# ADCduinoModule_ADC.net
KiCad netlist of a schematic drawn in Altium Designer
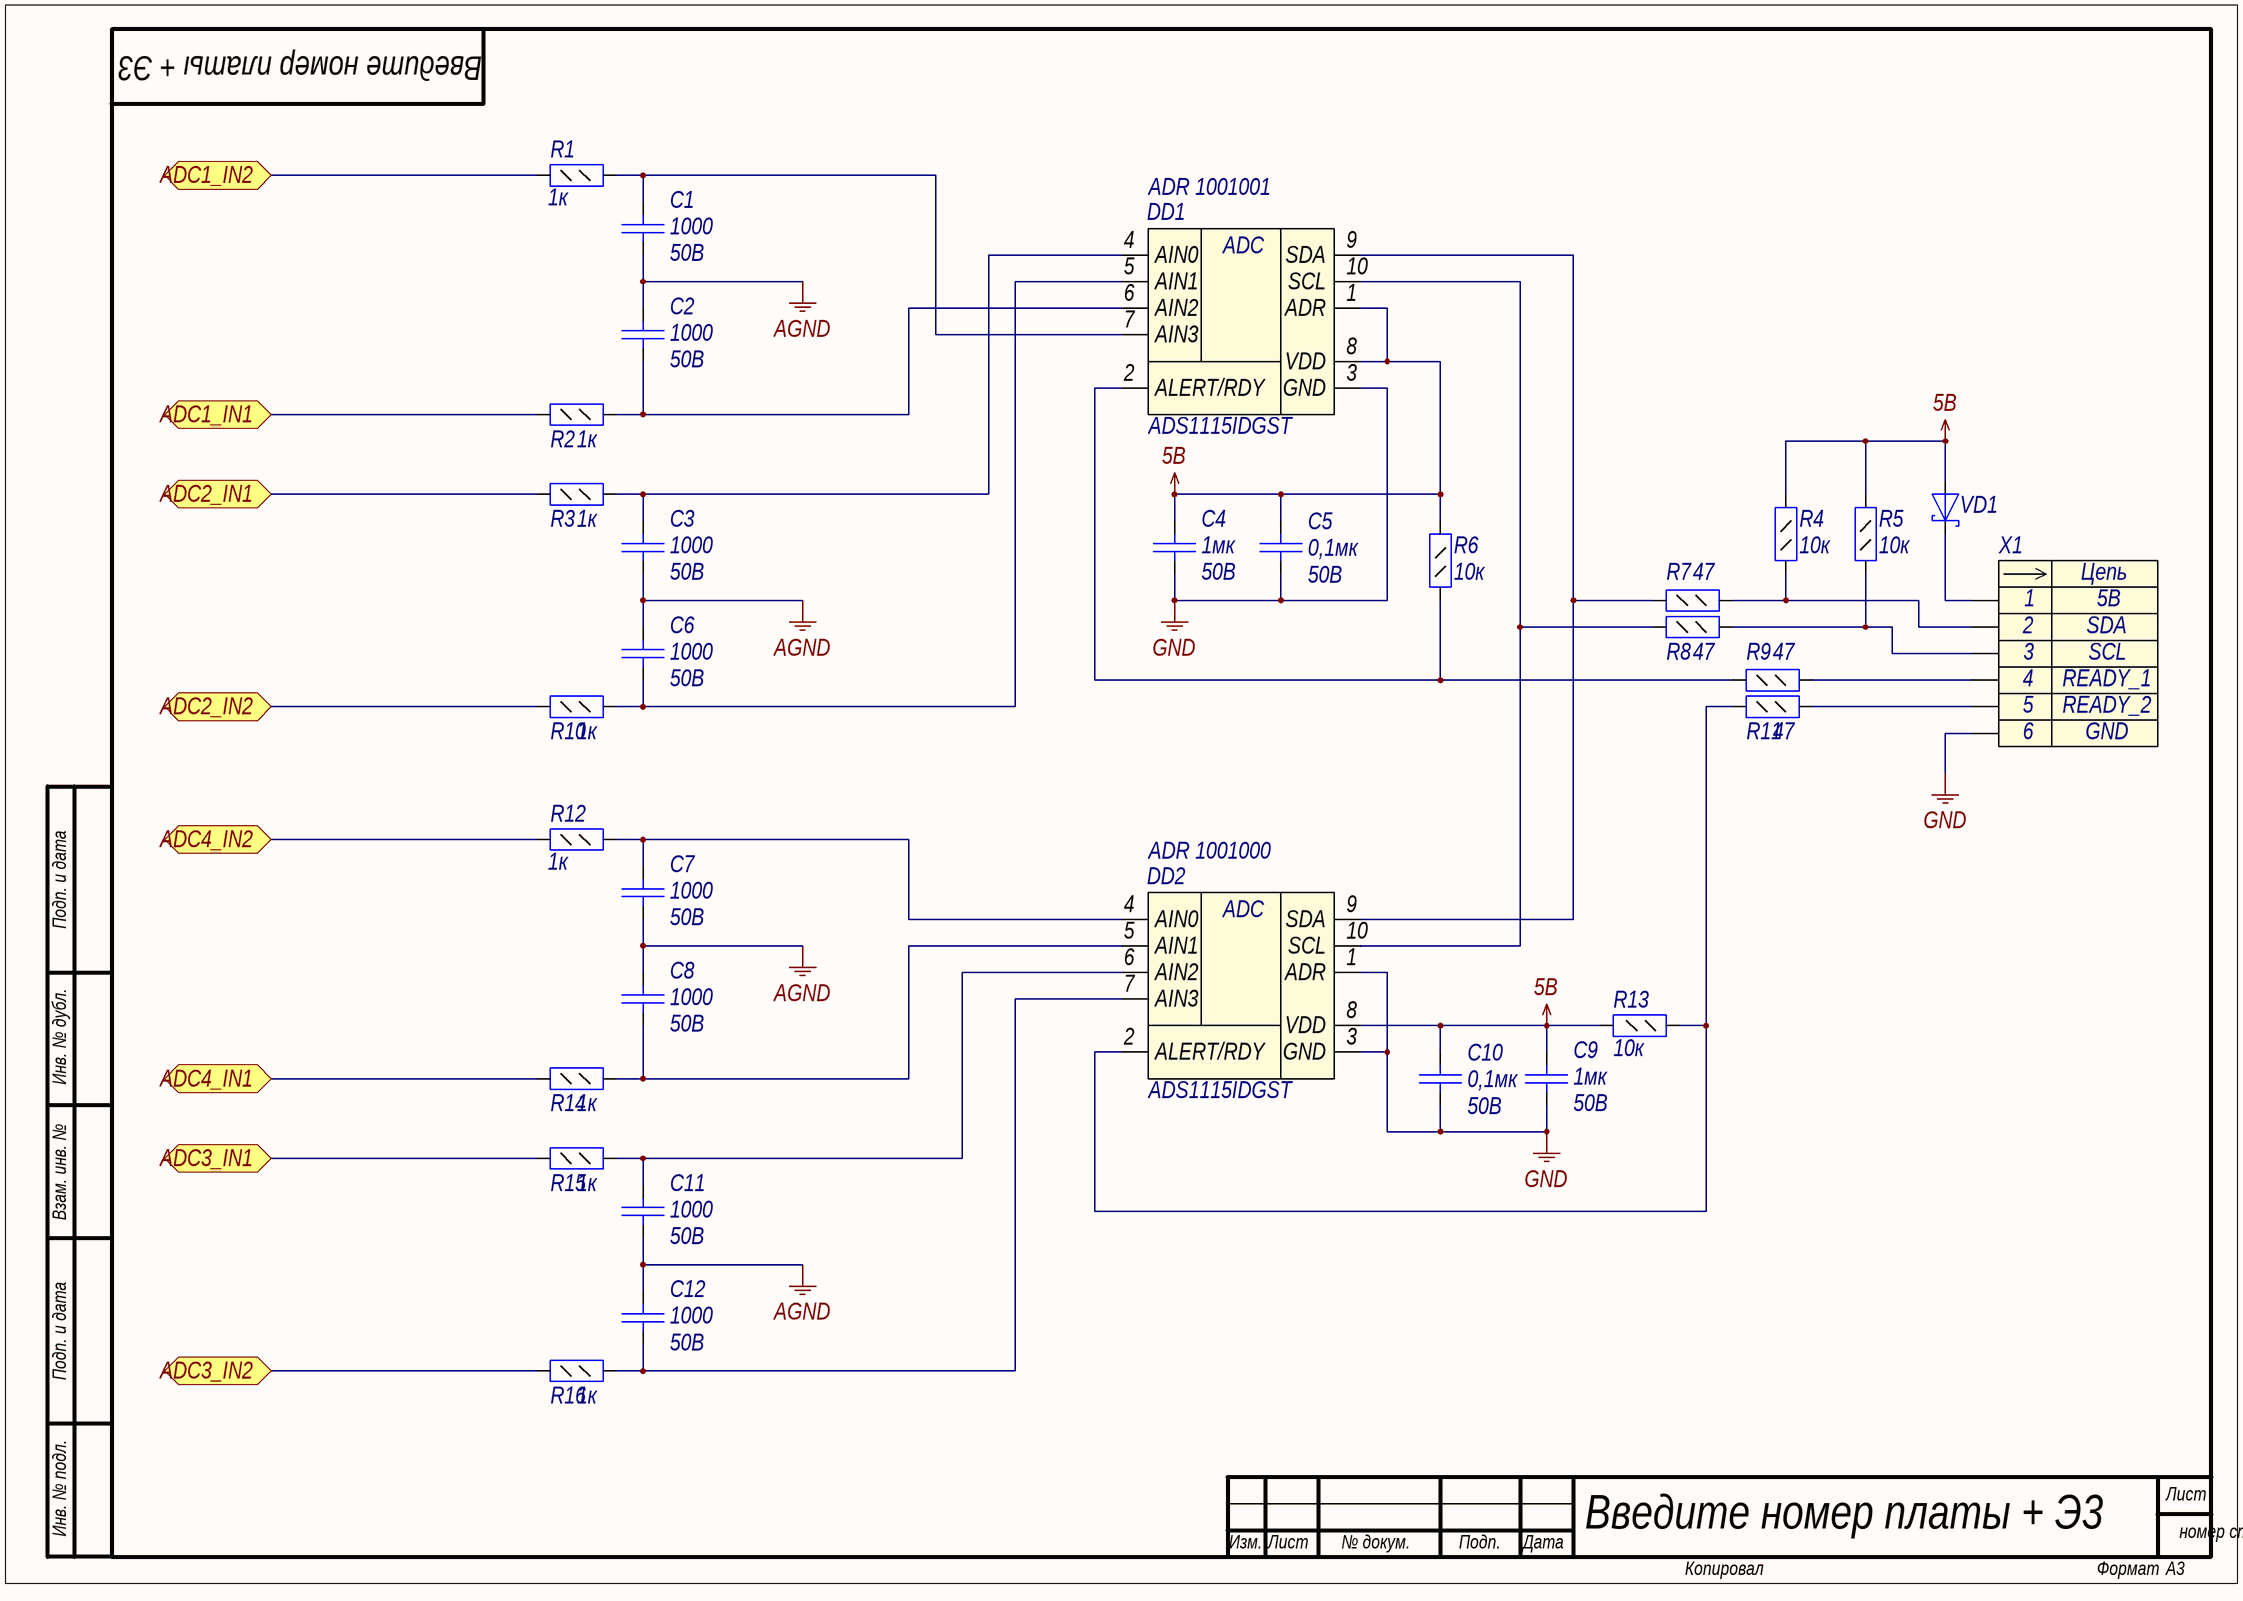
[diagram p0: ADCduinoModule_ADC.SchDoc]

(export (version "E")
  (design (tool "Eeschema 10.0.6"))
  (components
    (comp (ref "C1")
      (value "1000")
      (footprint "C0805")
      (description "Конденсатор")
      (fields
        (field (name "VOLTAGE") "50В")
        (field (name "PART NUMBER") "GRM216R71H102K*")
        (field (name "Comment") "Capacitor")
      )
      (libsource (lib "MOP44") (part "Capacitor"))
    )
    (comp (ref "C2")
      (value "1000")
      (footprint "C0805")
      (description "Конденсатор")
      (fields
        (field (name "VOLTAGE") "50В")
        (field (name "PART NUMBER") "GRM216R71H102K*")
        (field (name "Comment") "Capacitor")
      )
      (libsource (lib "MOP44") (part "Capacitor"))
    )
    (comp (ref "C3")
      (value "1000")
      (footprint "C0805")
      (description "Конденсатор")
      (fields
        (field (name "VOLTAGE") "50В")
        (field (name "PART NUMBER") "GRM216R71H102K*")
        (field (name "Comment") "Capacitor")
      )
      (libsource (lib "MOP44") (part "Capacitor"))
    )
    (comp (ref "C4")
      (value "1мк")
      (footprint "C0805")
      (description "Конденсатор")
      (fields
        (field (name "VOLTAGE") "50B")
        (field (name "PART NUMBER") "GRM21BR71H105K")
        (field (name "Comment") "Capacitor")
      )
      (libsource (lib "MOP44") (part "Capacitor"))
    )
    (comp (ref "C5")
      (value "0,1мк")
      (footprint "C0805")
      (description "Конденсатор")
      (fields
        (field (name "VOLTAGE") "50B")
        (field (name "PART NUMBER") "GRM21BR71H104K**")
        (field (name "Comment") "Capacitor")
      )
      (libsource (lib "MOP44") (part "Capacitor"))
    )
    (comp (ref "C6")
      (value "1000")
      (footprint "C0805")
      (description "Конденсатор")
      (fields
        (field (name "VOLTAGE") "50В")
        (field (name "PART NUMBER") "GRM216R71H102K*")
        (field (name "Comment") "Capacitor")
      )
      (libsource (lib "MOP44") (part "Capacitor"))
    )
    (comp (ref "C7")
      (value "1000")
      (footprint "C0805")
      (description "Конденсатор")
      (fields
        (field (name "VOLTAGE") "50В")
        (field (name "PART NUMBER") "GRM216R71H102K*")
        (field (name "Comment") "Capacitor")
      )
      (libsource (lib "MOP44") (part "Capacitor"))
    )
    (comp (ref "C8")
      (value "1000")
      (footprint "C0805")
      (description "Конденсатор")
      (fields
        (field (name "VOLTAGE") "50В")
        (field (name "PART NUMBER") "GRM216R71H102K*")
        (field (name "Comment") "Capacitor")
      )
      (libsource (lib "MOP44") (part "Capacitor"))
    )
    (comp (ref "C9")
      (value "1мк")
      (footprint "C0805")
      (description "Конденсатор")
      (fields
        (field (name "VOLTAGE") "50B")
        (field (name "PART NUMBER") "GRM21BR71H105K")
        (field (name "Comment") "Capacitor")
      )
      (libsource (lib "MOP44") (part "Capacitor"))
    )
    (comp (ref "C10")
      (value "0,1мк")
      (footprint "C0805")
      (description "Конденсатор")
      (fields
        (field (name "VOLTAGE") "50B")
        (field (name "PART NUMBER") "GRM21BR71H104K**")
        (field (name "Comment") "Capacitor")
      )
      (libsource (lib "MOP44") (part "Capacitor"))
    )
    (comp (ref "C11")
      (value "1000")
      (footprint "C0805")
      (description "Конденсатор")
      (fields
        (field (name "VOLTAGE") "50В")
        (field (name "PART NUMBER") "GRM216R71H102K*")
        (field (name "Comment") "Capacitor")
      )
      (libsource (lib "MOP44") (part "Capacitor"))
    )
    (comp (ref "C12")
      (value "1000")
      (footprint "C0805")
      (description "Конденсатор")
      (fields
        (field (name "VOLTAGE") "50В")
        (field (name "PART NUMBER") "GRM216R71H102K*")
        (field (name "Comment") "Capacitor")
      )
      (libsource (lib "MOP44") (part "Capacitor"))
    )
    (comp (ref "DD1")
      (value "ADS1115IDGST")
      (footprint "MSOP10")
      (description "Ultra-Small, Low-Power, 16-Bit  Analog-to-Digital Converter with Internal Reference")
      (libsource (lib "MOP44") (part "ADS1115IDGST"))
    )
    (comp (ref "DD2")
      (value "ADS1115IDGST")
      (footprint "MSOP10")
      (description "Ultra-Small, Low-Power, 16-Bit  Analog-to-Digital Converter with Internal Reference")
      (libsource (lib "MOP44") (part "ADS1115IDGST"))
    )
    (comp (ref "R1")
      (value "1к")
      (footprint "R0805")
      (description "Резистор")
      (fields (field (name "PART NUMBER") "RC0805FR-071KL") (field (name "POWER") "0,125Вт"))
      (libsource (lib "MOP44") (part "Resistor_0,125Вт"))
    )
    (comp (ref "R2")
      (value "1к")
      (footprint "R0805")
      (description "Резистор")
      (fields (field (name "PART NUMBER") "RC0805FR-071KL") (field (name "POWER") "0,125Вт"))
      (libsource (lib "MOP44") (part "Resistor_0,125Вт"))
    )
    (comp (ref "R3")
      (value "1к")
      (footprint "R0805")
      (description "Резистор")
      (fields (field (name "PART NUMBER") "RC0805FR-071KL") (field (name "POWER") "0,125Вт"))
      (libsource (lib "MOP44") (part "Resistor_0,125Вт"))
    )
    (comp (ref "R4")
      (value "10к")
      (footprint "R0805")
      (description "Резистор")
      (fields (field (name "PART NUMBER") "RC0805FR-0710KL") (field (name "POWER") "0,125Вт"))
      (libsource (lib "") (part "Resistor_0,125Вт_1"))
    )
    (comp (ref "R5")
      (value "10к")
      (footprint "R0805")
      (description "Резистор")
      (fields (field (name "PART NUMBER") "RC0805FR-0710KL") (field (name "POWER") "0,125Вт"))
      (libsource (lib "") (part "Resistor_0,125Вт_1"))
    )
    (comp (ref "R6")
      (value "10к")
      (footprint "R0805")
      (description "Резистор")
      (fields (field (name "PART NUMBER") "RC0805FR-0710KL") (field (name "POWER") "0,125Вт"))
      (libsource (lib "") (part "Resistor_0,125Вт_1"))
    )
    (comp (ref "R7")
      (value "47")
      (footprint "R0805")
      (description "Резистор")
      (fields (field (name "PART NUMBER") "RC0805FR-0747RL") (field (name "POWER") "0,125Вт"))
      (libsource (lib "MOP44") (part "Resistor_0,125Вт"))
    )
    (comp (ref "R8")
      (value "47")
      (footprint "R0805")
      (description "Резистор")
      (fields (field (name "PART NUMBER") "RC0805FR-0747RL") (field (name "POWER") "0,125Вт"))
      (libsource (lib "MOP44") (part "Resistor_0,125Вт"))
    )
    (comp (ref "R9")
      (value "47")
      (footprint "R0805")
      (description "Резистор")
      (fields (field (name "PART NUMBER") "RC0805FR-0747RL") (field (name "POWER") "0,125Вт"))
      (libsource (lib "MOP44") (part "Resistor_0,125Вт"))
    )
    (comp (ref "R10")
      (value "1к")
      (footprint "R0805")
      (description "Резистор")
      (fields (field (name "PART NUMBER") "RC0805FR-071KL") (field (name "POWER") "0,125Вт"))
      (libsource (lib "MOP44") (part "Resistor_0,125Вт"))
    )
    (comp (ref "R11")
      (value "47")
      (footprint "R0805")
      (description "Резистор")
      (fields (field (name "PART NUMBER") "RC0805FR-0747RL") (field (name "POWER") "0,125Вт"))
      (libsource (lib "MOP44") (part "Resistor_0,125Вт"))
    )
    (comp (ref "R12")
      (value "1к")
      (footprint "R0805")
      (description "Резистор")
      (fields (field (name "PART NUMBER") "RC0805FR-071KL") (field (name "POWER") "0,125Вт"))
      (libsource (lib "MOP44") (part "Resistor_0,125Вт"))
    )
    (comp (ref "R13")
      (value "10к")
      (footprint "R0805")
      (description "Резистор")
      (fields (field (name "PART NUMBER") "RC0805FR-0710KL") (field (name "POWER") "0,125Вт"))
      (libsource (lib "") (part "Resistor_0,125Вт_2"))
    )
    (comp (ref "R14")
      (value "1к")
      (footprint "R0805")
      (description "Резистор")
      (fields (field (name "PART NUMBER") "RC0805FR-071KL") (field (name "POWER") "0,125Вт"))
      (libsource (lib "MOP44") (part "Resistor_0,125Вт"))
    )
    (comp (ref "R15")
      (value "1к")
      (footprint "R0805")
      (description "Резистор")
      (fields (field (name "PART NUMBER") "RC0805FR-071KL") (field (name "POWER") "0,125Вт"))
      (libsource (lib "MOP44") (part "Resistor_0,125Вт"))
    )
    (comp (ref "R16")
      (value "1к")
      (footprint "R0805")
      (description "Резистор")
      (fields (field (name "PART NUMBER") "RC0805FR-071KL") (field (name "POWER") "0,125Вт"))
      (libsource (lib "MOP44") (part "Resistor_0,125Вт"))
    )
    (comp (ref "VD1")
      (value "DiodeSchottky")
      (footprint "SMA")
      (description "Диод Шоттки")
      (fields (field (name "PART NUMBER") "SK34A"))
      (libsource (lib "MOP44") (part "DiodeSchottky"))
    )
    (comp (ref "X1")
      (value "Header_6_plg")
      (footprint "PLS-6")
      (description "Разъем - 6 конт. вилка")
      (fields (field (name "PART NUMBER") "DS1021-1*6SF112-B"))
      (libsource (lib "MOP44") (part "Header_6_plg"))
    )
  )
  (nets
    (net (code "1") (name "/ADC1_IN1") (class "Default")
      (node (ref "R2") (pin "1") (pinfunction "1_1") (pintype "passive"))
    )
    (net (code "2") (name "/ADC1_IN2") (class "Default")
      (node (ref "R1") (pin "1") (pinfunction "1_1") (pintype "passive"))
    )
    (net (code "3") (name "/ADC2_IN1") (class "Default")
      (node (ref "R3") (pin "1") (pinfunction "1_1") (pintype "passive"))
    )
    (net (code "4") (name "/ADC2_IN2") (class "Default")
      (node (ref "R10") (pin "1") (pinfunction "1_1") (pintype "passive"))
    )
    (net (code "5") (name "/ADC3_IN1") (class "Default")
      (node (ref "R15") (pin "1") (pinfunction "1_1") (pintype "passive"))
    )
    (net (code "6") (name "/ADC3_IN2") (class "Default")
      (node (ref "R16") (pin "1") (pinfunction "1_1") (pintype "passive"))
    )
    (net (code "7") (name "/ADC4_IN1") (class "Default")
      (node (ref "R14") (pin "1") (pinfunction "1_1") (pintype "passive"))
    )
    (net (code "8") (name "/ADC4_IN2") (class "Default")
      (node (ref "R12") (pin "1") (pinfunction "1_1") (pintype "passive"))
    )
    (net (code "9") (name "5B") (class "Default")
      (node (ref "C10") (pin "2") (pinfunction "2_2") (pintype "passive"))
      (node (ref "C4") (pin "2") (pinfunction "2_2") (pintype "passive"))
      (node (ref "C5") (pin "2") (pinfunction "2_2") (pintype "passive"))
      (node (ref "C9") (pin "2") (pinfunction "2_2") (pintype "passive"))
      (node (ref "DD1") (pin "1") (pinfunction "ADR_1") (pintype "power_in"))
      (node (ref "DD1") (pin "8") (pinfunction "VDD_8") (pintype "power_in"))
      (node (ref "DD2") (pin "8") (pinfunction "VDD_8") (pintype "power_in"))
      (node (ref "R13") (pin "2") (pinfunction "2_2") (pintype "passive"))
      (node (ref "R4") (pin "2") (pinfunction "2_2") (pintype "passive"))
      (node (ref "R5") (pin "2") (pinfunction "2_2") (pintype "passive"))
      (node (ref "R6") (pin "2") (pinfunction "2_2") (pintype "passive"))
      (node (ref "VD1") (pin "2") (pinfunction "A_2") (pintype "passive"))
    )
    (net (code "10") (name "AGND") (class "Default")
      (node (ref "C1") (pin "1") (pinfunction "1_1") (pintype "passive"))
      (node (ref "C11") (pin "1") (pinfunction "1_1") (pintype "passive"))
      (node (ref "C12") (pin "2") (pinfunction "2_2") (pintype "passive"))
      (node (ref "C2") (pin "2") (pinfunction "2_2") (pintype "passive"))
      (node (ref "C3") (pin "1") (pinfunction "1_1") (pintype "passive"))
      (node (ref "C6") (pin "2") (pinfunction "2_2") (pintype "passive"))
      (node (ref "C7") (pin "1") (pinfunction "1_1") (pintype "passive"))
      (node (ref "C8") (pin "2") (pinfunction "2_2") (pintype "passive"))
    )
    (net (code "11") (name "GND") (class "Default")
      (node (ref "C10") (pin "1") (pinfunction "1_1") (pintype "passive"))
      (node (ref "C4") (pin "1") (pinfunction "1_1") (pintype "passive"))
      (node (ref "C5") (pin "1") (pinfunction "1_1") (pintype "passive"))
      (node (ref "C9") (pin "1") (pinfunction "1_1") (pintype "passive"))
      (node (ref "DD1") (pin "3") (pinfunction "GND_3") (pintype "power_in"))
      (node (ref "DD2") (pin "1") (pinfunction "ADR_1") (pintype "power_in"))
      (node (ref "DD2") (pin "3") (pinfunction "GND_3") (pintype "power_in"))
      (node (ref "X1") (pin "6") (pinfunction "6_6") (pintype "passive"))
    )
    (net (code "12") (name "Net-(DD1-AIN0)") (class "Default")
      (node (ref "C3") (pin "2") (pinfunction "2_2") (pintype "passive"))
      (node (ref "DD1") (pin "4") (pinfunction "AIN0_4") (pintype "power_in"))
      (node (ref "R3") (pin "2") (pinfunction "2_2") (pintype "passive"))
    )
    (net (code "13") (name "Net-(DD1-AIN1)") (class "Default")
      (node (ref "C6") (pin "1") (pinfunction "1_1") (pintype "passive"))
      (node (ref "DD1") (pin "5") (pinfunction "AIN1_5") (pintype "power_in"))
      (node (ref "R10") (pin "2") (pinfunction "2_2") (pintype "passive"))
    )
    (net (code "14") (name "Net-(DD1-AIN2)") (class "Default")
      (node (ref "C2") (pin "1") (pinfunction "1_1") (pintype "passive"))
      (node (ref "DD1") (pin "6") (pinfunction "AIN2_6") (pintype "power_in"))
      (node (ref "R2") (pin "2") (pinfunction "2_2") (pintype "passive"))
    )
    (net (code "15") (name "Net-(DD1-AIN3)") (class "Default")
      (node (ref "C1") (pin "2") (pinfunction "2_2") (pintype "passive"))
      (node (ref "DD1") (pin "7") (pinfunction "AIN3_7") (pintype "power_in"))
      (node (ref "R1") (pin "2") (pinfunction "2_2") (pintype "passive"))
    )
    (net (code "16") (name "Net-(DD1-ALERT{slash}RDY)") (class "Default")
      (node (ref "DD1") (pin "2") (pinfunction "ALERT/RDY_2") (pintype "power_in"))
      (node (ref "R6") (pin "1") (pinfunction "1_1") (pintype "passive"))
      (node (ref "R9") (pin "1") (pinfunction "1_1") (pintype "passive"))
    )
    (net (code "17") (name "Net-(DD1-SCL)") (class "Default")
      (node (ref "DD1") (pin "10") (pinfunction "SCL_10") (pintype "power_in"))
      (node (ref "DD2") (pin "10") (pinfunction "SCL_10") (pintype "power_in"))
      (node (ref "R8") (pin "1") (pinfunction "1_1") (pintype "passive"))
    )
    (net (code "18") (name "Net-(DD1-SDA)") (class "Default")
      (node (ref "DD1") (pin "9") (pinfunction "SDA_9") (pintype "power_in"))
      (node (ref "DD2") (pin "9") (pinfunction "SDA_9") (pintype "power_in"))
      (node (ref "R7") (pin "1") (pinfunction "1_1") (pintype "passive"))
    )
    (net (code "19") (name "Net-(DD2-AIN0)") (class "Default")
      (node (ref "C7") (pin "2") (pinfunction "2_2") (pintype "passive"))
      (node (ref "DD2") (pin "4") (pinfunction "AIN0_4") (pintype "power_in"))
      (node (ref "R12") (pin "2") (pinfunction "2_2") (pintype "passive"))
    )
    (net (code "20") (name "Net-(DD2-AIN1)") (class "Default")
      (node (ref "C8") (pin "1") (pinfunction "1_1") (pintype "passive"))
      (node (ref "DD2") (pin "5") (pinfunction "AIN1_5") (pintype "power_in"))
      (node (ref "R14") (pin "2") (pinfunction "2_2") (pintype "passive"))
    )
    (net (code "21") (name "Net-(DD2-AIN2)") (class "Default")
      (node (ref "C11") (pin "2") (pinfunction "2_2") (pintype "passive"))
      (node (ref "DD2") (pin "6") (pinfunction "AIN2_6") (pintype "power_in"))
      (node (ref "R15") (pin "2") (pinfunction "2_2") (pintype "passive"))
    )
    (net (code "22") (name "Net-(DD2-AIN3)") (class "Default")
      (node (ref "C12") (pin "1") (pinfunction "1_1") (pintype "passive"))
      (node (ref "DD2") (pin "7") (pinfunction "AIN3_7") (pintype "power_in"))
      (node (ref "R16") (pin "2") (pinfunction "2_2") (pintype "passive"))
    )
    (net (code "23") (name "Net-(DD2-ALERT{slash}RDY)") (class "Default")
      (node (ref "DD2") (pin "2") (pinfunction "ALERT/RDY_2") (pintype "power_in"))
      (node (ref "R11") (pin "1") (pinfunction "1_1") (pintype "passive"))
      (node (ref "R13") (pin "1") (pinfunction "1_1") (pintype "passive"))
    )
    (net (code "24") (name "Net-(R4-Pad1)") (class "Default")
      (node (ref "R4") (pin "1") (pinfunction "1_1") (pintype "passive"))
      (node (ref "R7") (pin "2") (pinfunction "2_2") (pintype "passive"))
      (node (ref "X1") (pin "2") (pinfunction "2_2") (pintype "passive"))
    )
    (net (code "25") (name "Net-(R5-Pad1)") (class "Default")
      (node (ref "R5") (pin "1") (pinfunction "1_1") (pintype "passive"))
      (node (ref "R8") (pin "2") (pinfunction "2_2") (pintype "passive"))
      (node (ref "X1") (pin "3") (pinfunction "3_3") (pintype "passive"))
    )
    (net (code "26") (name "Net-(R9-Pad2)") (class "Default")
      (node (ref "R9") (pin "2") (pinfunction "2_2") (pintype "passive"))
      (node (ref "X1") (pin "4") (pinfunction "4_4") (pintype "passive"))
    )
    (net (code "27") (name "Net-(R11-Pad2)") (class "Default")
      (node (ref "R11") (pin "2") (pinfunction "2_2") (pintype "passive"))
      (node (ref "X1") (pin "5") (pinfunction "5_5") (pintype "passive"))
    )
    (net (code "28") (name "Net-(VD1-K)") (class "Default")
      (node (ref "VD1") (pin "1") (pinfunction "K_1") (pintype "passive"))
      (node (ref "X1") (pin "1") (pinfunction "1_1") (pintype "passive"))
    )
  )
)
